# Shining_Pig.net
KiCad netlist of a schematic drawn in Altium Designer
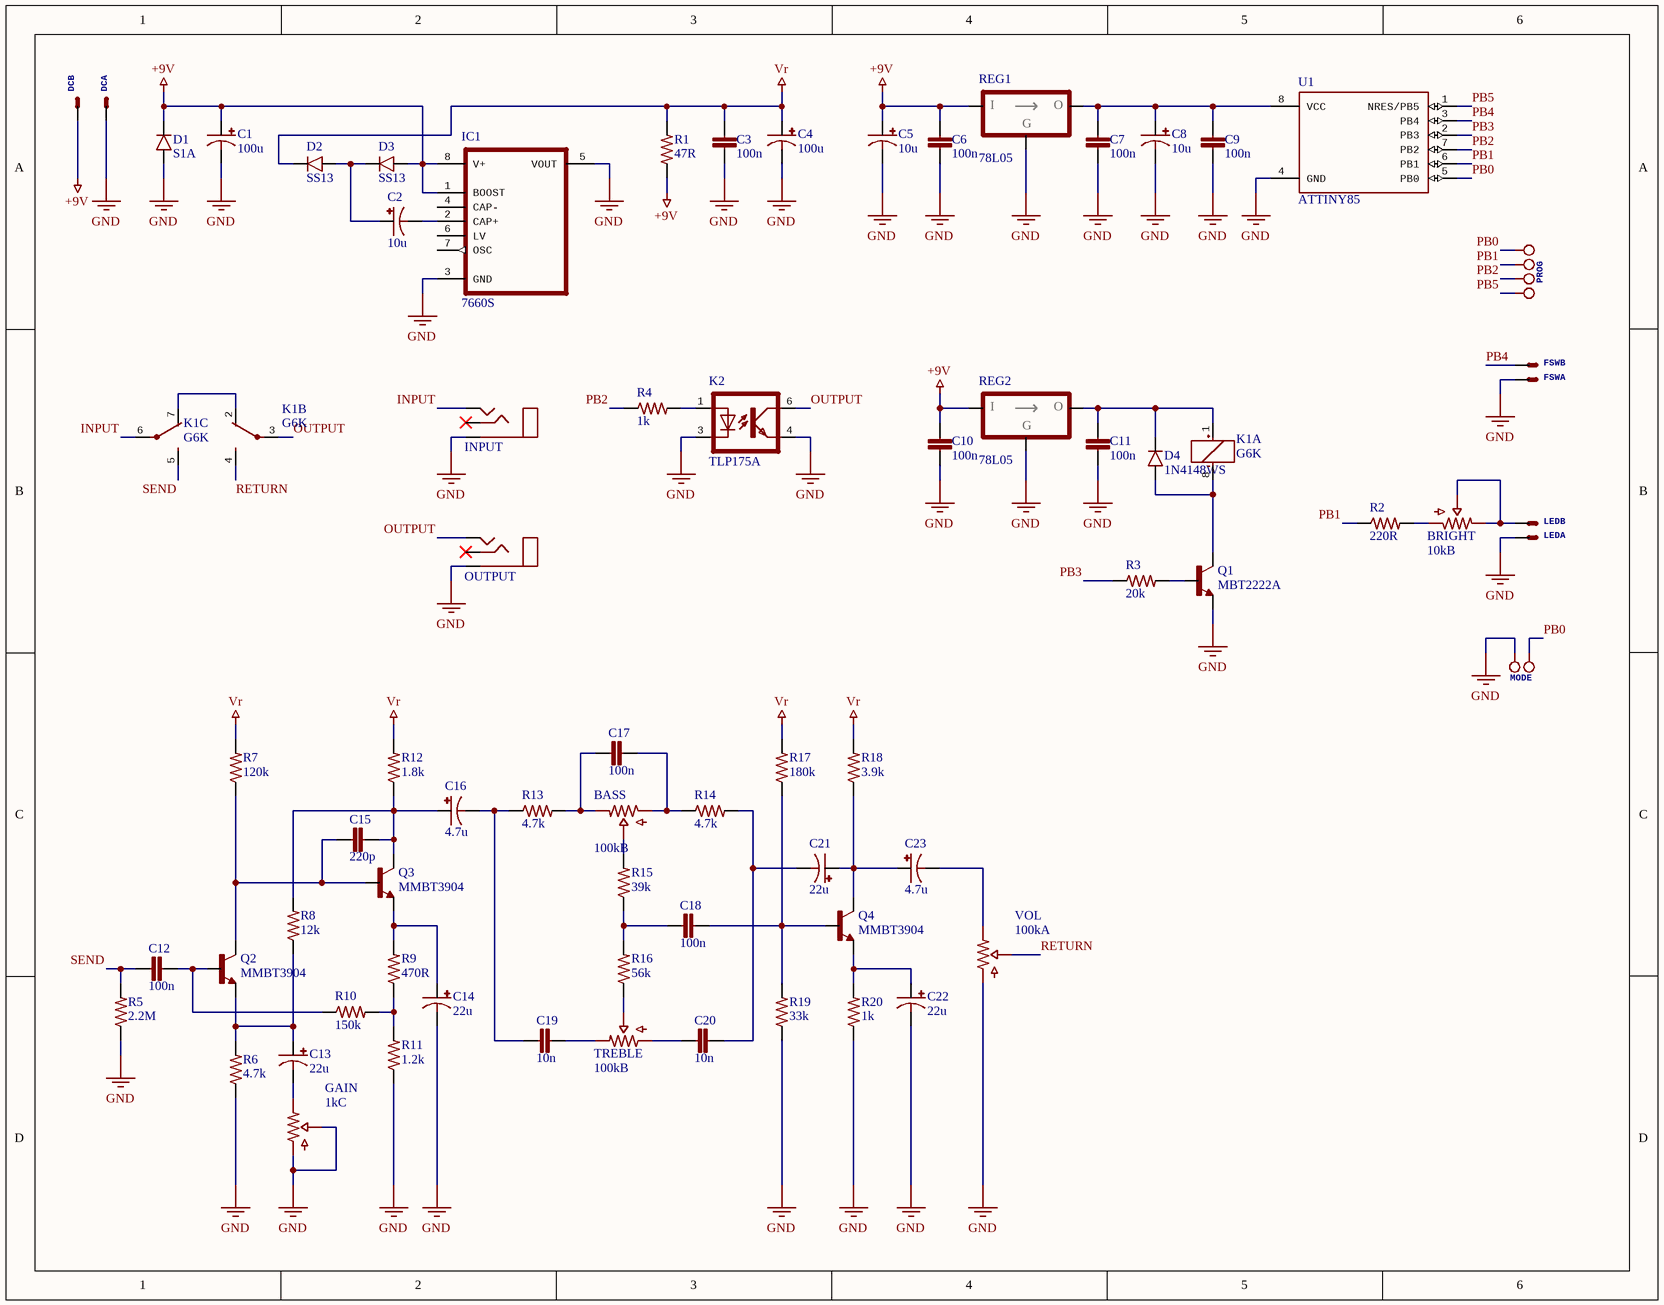
[diagram p0: Shining Pig.SchDoc]

(export (version "E")
  (design (tool "Eeschema 10.0.6"))
  (components
    (comp (ref "BASS")
      (value "100kB")
      (footprint "ALPHA_16mm_BOTTOM")
      (description "100k Lin potentiometer round shaft")
      (libsource (lib "Pedals") (part "POT_100kB_ALPHA_16mm"))
    )
    (comp (ref "BRIGHT")
      (value "10kB")
      (footprint "BOURNS_3362P")
      (description "10k Lin 3362P trimmer")
      (libsource (lib "Pedals") (part "TRIM_10kB_3362P"))
    )
    (comp (ref "C1")
      (value "100u")
      (footprint "CAPAE_D")
      (description "CAP ALUM 100UF 25V SMD")
      (fields
        (field (name "MANUFACTURER") "Multicomp")
        (field (name "MANUFACTURER PART NUMBER") "MCVVT025M101EA6L")
      )
      (libsource (lib "Pedals SMD") (part "MCVVT025M101EA6L"))
    )
    (comp (ref "C2")
      (value "10u")
      (footprint "CAPAE_B")
      (description "CAP ALUM 10UF 25V SMD")
      (fields
        (field (name "MANUFACTURER") "Multicomp")
        (field (name "MANUFACTURER PART NUMBER") "MCVVT025M100CA1L")
      )
      (libsource (lib "") (part "MCVVT025M100CA1L_1"))
    )
    (comp (ref "C3")
      (value "100n")
      (footprint "CHIP_0603")
      (description "CAP CER 100NF 50V X7R 0603")
      (fields
        (field (name "MANUFACTURER") "Multicomp")
        (field (name "MANUFACTURER PART NUMBER") "MC0603B104K500CT")
      )
      (libsource (lib "Pedals SMD") (part "MC0603B104K500CT"))
    )
    (comp (ref "C4")
      (value "100u")
      (footprint "CAPAE_D")
      (description "CAP ALUM 100UF 25V SMD")
      (fields
        (field (name "MANUFACTURER") "Multicomp")
        (field (name "MANUFACTURER PART NUMBER") "MCVVT025M101EA6L")
      )
      (libsource (lib "Pedals SMD") (part "MCVVT025M101EA6L"))
    )
    (comp (ref "C5")
      (value "10u")
      (footprint "CAPAE_B")
      (description "CAP ALUM 10UF 25V SMD")
      (fields
        (field (name "MANUFACTURER") "Multicomp")
        (field (name "MANUFACTURER PART NUMBER") "MCVVT025M100CA1L")
      )
      (libsource (lib "Pedals SMD") (part "MCVVT025M100CA1L"))
    )
    (comp (ref "C6")
      (value "100n")
      (footprint "CHIP_0603")
      (description "CAP CER 100NF 50V X7R 0603")
      (fields
        (field (name "MANUFACTURER") "Multicomp")
        (field (name "MANUFACTURER PART NUMBER") "MC0603B104K500CT")
      )
      (libsource (lib "Pedals SMD") (part "MC0603B104K500CT"))
    )
    (comp (ref "C7")
      (value "100n")
      (footprint "CHIP_0603")
      (description "CAP CER 100NF 50V X7R 0603")
      (fields
        (field (name "MANUFACTURER") "Multicomp")
        (field (name "MANUFACTURER PART NUMBER") "MC0603B104K500CT")
      )
      (libsource (lib "Pedals SMD") (part "MC0603B104K500CT"))
    )
    (comp (ref "C8")
      (value "10u")
      (footprint "CAPAE_B")
      (description "CAP ALUM 10UF 25V SMD")
      (fields
        (field (name "MANUFACTURER") "Multicomp")
        (field (name "MANUFACTURER PART NUMBER") "MCVVT025M100CA1L")
      )
      (libsource (lib "Pedals SMD") (part "MCVVT025M100CA1L"))
    )
    (comp (ref "C9")
      (value "100n")
      (footprint "CHIP_0603")
      (description "CAP CER 100NF 50V X7R 0603")
      (fields
        (field (name "MANUFACTURER") "Multicomp")
        (field (name "MANUFACTURER PART NUMBER") "MC0603B104K500CT")
      )
      (libsource (lib "Pedals SMD") (part "MC0603B104K500CT"))
    )
    (comp (ref "C10")
      (value "100n")
      (footprint "CHIP_0603")
      (description "CAP CER 100NF 50V X7R 0603")
      (fields
        (field (name "MANUFACTURER") "Multicomp")
        (field (name "MANUFACTURER PART NUMBER") "MC0603B104K500CT")
      )
      (libsource (lib "Pedals SMD") (part "MC0603B104K500CT"))
    )
    (comp (ref "C11")
      (value "100n")
      (footprint "CHIP_0603")
      (description "CAP CER 100NF 50V X7R 0603")
      (fields
        (field (name "MANUFACTURER") "Multicomp")
        (field (name "MANUFACTURER PART NUMBER") "MC0603B104K500CT")
      )
      (libsource (lib "Pedals SMD") (part "MC0603B104K500CT"))
    )
    (comp (ref "C12")
      (value "100n")
      (footprint "CHIP_1206")
      (description "CAP CER 100NF 50V C0G/NP0 1206")
      (fields
        (field (name "MANUFACTURER") "Murata")
        (field (name "MANUFACTURER PART NUMBER") "GRM31C5C1H104JA01L")
      )
      (libsource (lib "Pedals SMD") (part "GRM31C5C1H104JA01L"))
    )
    (comp (ref "C13")
      (value "22u")
      (footprint "CAPAE_D")
      (description "CAP ALUM 22UF 20% 35V LESR SMD")
      (fields
        (field (name "MANUFACTURER") "Panasonic")
        (field (name "MANUFACTURER PART NUMBER") "EEEFC1V220AP")
      )
      (libsource (lib "") (part "EEEFC1V220AP_1"))
    )
    (comp (ref "C14")
      (value "22u")
      (footprint "CAPAE_D")
      (description "CAP ALUM 22UF 20% 35V LESR SMD")
      (fields
        (field (name "MANUFACTURER") "Panasonic")
        (field (name "MANUFACTURER PART NUMBER") "EEEFC1V220AP")
      )
      (libsource (lib "") (part "EEEFC1V220AP_1"))
    )
    (comp (ref "C15")
      (value "220p")
      (footprint "CHIP_0603")
      (description "CAP CER 220PF 50V C0G/NP0 0603")
      (fields
        (field (name "MANUFACTURER") "Multicomp")
        (field (name "MANUFACTURER PART NUMBER") "MC0603N221J500CT")
      )
      (libsource (lib "Pedals SMD") (part "MC0603N221J500CT"))
    )
    (comp (ref "C16")
      (value "4.7u")
      (footprint "CAPAE_C")
      (description "CAP ALUM 4.7UF 50V LESR SMD")
      (fields
        (field (name "MANUFACTURER") "Panasonic")
        (field (name "MANUFACTURER PART NUMBER") "EEEFC1H4R7R")
      )
      (libsource (lib "Pedals SMD") (part "EEEFC1H4R7R"))
    )
    (comp (ref "C17")
      (value "100n")
      (footprint "CHIP_1206")
      (description "CAP CER 100NF 50V C0G/NP0 1206")
      (fields
        (field (name "MANUFACTURER") "Murata")
        (field (name "MANUFACTURER PART NUMBER") "GRM31C5C1H104JA01L")
      )
      (libsource (lib "Pedals SMD") (part "GRM31C5C1H104JA01L"))
    )
    (comp (ref "C18")
      (value "100n")
      (footprint "CHIP_1206")
      (description "CAP CER 100NF 50V C0G/NP0 1206")
      (fields
        (field (name "MANUFACTURER") "Murata")
        (field (name "MANUFACTURER PART NUMBER") "GRM31C5C1H104JA01L")
      )
      (libsource (lib "Pedals SMD") (part "GRM31C5C1H104JA01L"))
    )
    (comp (ref "C19")
      (value "10n")
      (footprint "CHIP_0603")
      (description "CAP CER 10NF 50V C0G/NP0 0603")
      (fields
        (field (name "MANUFACTURER") "Murata")
        (field (name "MANUFACTURER PART NUMBER") "GRM1885C1H103JA01D")
      )
      (libsource (lib "Pedals SMD") (part "GRM1885C1H103JA01D"))
    )
    (comp (ref "C20")
      (value "10n")
      (footprint "CHIP_0603")
      (description "CAP CER 10NF 50V C0G/NP0 0603")
      (fields
        (field (name "MANUFACTURER") "Murata")
        (field (name "MANUFACTURER PART NUMBER") "GRM1885C1H103JA01D")
      )
      (libsource (lib "Pedals SMD") (part "GRM1885C1H103JA01D"))
    )
    (comp (ref "C21")
      (value "22u")
      (footprint "CAPAE_D")
      (description "CAP ALUM 22UF 20% 35V LESR SMD")
      (fields
        (field (name "MANUFACTURER") "Panasonic")
        (field (name "MANUFACTURER PART NUMBER") "EEEFC1V220AP")
      )
      (libsource (lib "Pedals SMD") (part "EEEFC1V220AP"))
    )
    (comp (ref "C22")
      (value "22u")
      (footprint "CAPAE_D")
      (description "CAP ALUM 22UF 20% 35V LESR SMD")
      (fields
        (field (name "MANUFACTURER") "Panasonic")
        (field (name "MANUFACTURER PART NUMBER") "EEEFC1V220AP")
      )
      (libsource (lib "") (part "EEEFC1V220AP_1"))
    )
    (comp (ref "C23")
      (value "4.7u")
      (footprint "CAPAE_C")
      (description "CAP ALUM 4.7UF 50V LESR SMD")
      (fields
        (field (name "MANUFACTURER") "Panasonic")
        (field (name "MANUFACTURER PART NUMBER") "EEEFC1H4R7R")
      )
      (libsource (lib "Pedals SMD") (part "EEEFC1H4R7R"))
    )
    (comp (ref "D1")
      (value "S1A")
      (footprint "DO214")
      (description "DIODE GEN PURP 50V 1A SMA")
      (fields (field (name "MANUFACTURER") "ON Semiconductor / Fairchild"))
      (libsource (lib "Pedals SMD") (part "S1A"))
    )
    (comp (ref "D2")
      (value "SS13")
      (footprint "SOD123F")
      (description "DIODE SCHOTTKY 30V 1A SOD123F")
      (fields
        (field (name "MANUFACTURER") "ON Semiconductor / Fairchild")
        (field (name "MANUFACTURER PART NUMBER") "SS13FL")
      )
      (libsource (lib "Pedals SMD") (part "SS13FL"))
    )
    (comp (ref "D3")
      (value "SS13")
      (footprint "SOD123F")
      (description "DIODE SCHOTTKY 30V 1A SOD123F")
      (fields
        (field (name "MANUFACTURER") "ON Semiconductor / Fairchild")
        (field (name "MANUFACTURER PART NUMBER") "SS13FL")
      )
      (libsource (lib "Pedals SMD") (part "SS13FL"))
    )
    (comp (ref "D4")
      (value "1N4148WS")
      (footprint "SOD323")
      (description "DIODE GEN PURP 75V 150MA SOD323F")
      (fields (field (name "MANUFACTURER") "ON Semiconductor / Fairchild"))
      (libsource (lib "Pedals SMD") (part "1N4148WS"))
    )
    (comp (ref "DC")
      (value "J_JST-XH-02")
      (footprint "JST-XH-02")
      (description "2 Pins male XH header")
      (libsource (lib "Pedals") (part "J_JST-XH-02"))
    )
    (comp (ref "FSW")
      (value "J_JST-XH-02")
      (footprint "JST-XH-02")
      (description "2 Pins male XH header")
      (libsource (lib "Pedals") (part "J_JST-XH-02"))
    )
    (comp (ref "GAIN")
      (value "1kC")
      (footprint "ALPHA_16mm_BOTTOM")
      (description "1k Reverse log potentiometer round shaft")
      (libsource (lib "Pedals") (part "POT_1kC_ALPHA_16mm"))
    )
    (comp (ref "IC1")
      (value "7660S")
      (footprint "SO8")
      (description "RENESAS - ICL7660SCBAZ - IC DC DC CHARGE PUMP")
      (fields
        (field (name "MANUFACTURER") "Intersil")
        (field (name "MANUFACTURER PART NUMBER") "ICL7660SCBAZ")
      )
      (libsource (lib "Pedals SMD") (part "ICL7660SCBAZ"))
    )
    (comp (ref "INPUT")
      (value "J_STEREO")
      (footprint "STEREO")
      (description "6.35mm stereo insulated socket jack PCB mounted")
      (libsource (lib "Pedals") (part "J_STEREO"))
    )
    (comp (ref "K1")
      (value "G6K")
      (footprint "G6K")
      (description "OMRON - G6K-2F 5DC - RELAY, SIGNAL, DPDT, 30VDC, 1A")
      (fields (field (name "MANUFACTURER") "Cliff") (field (name "MANUFACTURER PART NUMBER") "G6K-2F5DC"))
      (libsource (lib "") (part "G6K-2F5DC_2"))
    )
    (comp (ref "K2")
      (value "TLP175A")
      (footprint "TLP175A")
      (description "Toshiba TLP175A AC Input MOSFET Output Optocoupler, Surface Mount, 4-Pin SOIC")
      (fields (field (name "MANUFACTURER") "Toshiba"))
      (libsource (lib "Pedals SMD") (part "TLP175A"))
    )
    (comp (ref "LED")
      (value "J_JST-XH-02")
      (footprint "JST-XH-02")
      (description "2 Pins male XH header")
      (libsource (lib "Pedals") (part "J_JST-XH-02"))
    )
    (comp (ref "MODE")
      (value "J_HEADER_2PINS")
      (footprint "HEADER_2PINS")
      (description "2 Pins male header")
      (libsource (lib "Pedals") (part "J_HEADER_2PINS"))
    )
    (comp (ref "OUTPUT")
      (value "J_STEREO")
      (footprint "STEREO")
      (description "6.35mm stereo insulated socket jack PCB mounted")
      (libsource (lib "Pedals") (part "J_STEREO"))
    )
    (comp (ref "PROG")
      (value "J_HEADER_4PINS_FEM")
      (footprint "HEADER_4Pins_FEM")
      (description "4 Pins female header")
      (libsource (lib "Pedals") (part "J_HEADER_4PINS_FEM"))
    )
    (comp (ref "Q1")
      (value "MBT2222A")
      (footprint "SOT323")
      (description "TRANS NPN 40V 0.6A SOT323")
      (fields
        (field (name "MANUFACTURER") "ON Semiconductor")
        (field (name "MANUFACTURER PART NUMBER") "MMBT2222AWT1G")
      )
      (libsource (lib "Pedals SMD") (part "MMBT2222AWT1G"))
    )
    (comp (ref "Q2")
      (value "MMBT3904")
      (footprint "SOT23")
      (description "TRANS NPN 40V 0.2A SOT23")
      (fields
        (field (name "MANUFACTURER") "ON Semiconductor")
        (field (name "MANUFACTURER PART NUMBER") "MMBT3904LT1G")
      )
      (libsource (lib "Pedals SMD") (part "MMBT3904LT1G"))
    )
    (comp (ref "Q3")
      (value "MMBT3904")
      (footprint "SOT23")
      (description "TRANS NPN 40V 0.2A SOT23")
      (fields
        (field (name "MANUFACTURER") "ON Semiconductor")
        (field (name "MANUFACTURER PART NUMBER") "MMBT3904LT1G")
      )
      (libsource (lib "Pedals SMD") (part "MMBT3904LT1G"))
    )
    (comp (ref "Q4")
      (value "MMBT3904")
      (footprint "SOT23")
      (description "TRANS NPN 40V 0.2A SOT23")
      (fields
        (field (name "MANUFACTURER") "ON Semiconductor")
        (field (name "MANUFACTURER PART NUMBER") "MMBT3904LT1G")
      )
      (libsource (lib "Pedals SMD") (part "MMBT3904LT1G"))
    )
    (comp (ref "R1")
      (value "47R")
      (footprint "CHIP_R_1206")
      (description "RES SMD 47 OHM 1% 1/4W 1206")
      (fields
        (field (name "MANUFACTURER") "Vishay")
        (field (name "MANUFACTURER PART NUMBER") "CRCW120647R0FKEA")
      )
      (libsource (lib "Pedals SMD") (part "CRCW120647R0FKEA"))
    )
    (comp (ref "R2")
      (value "220R")
      (footprint "CHIP_R_1206")
      (description "RES SMD 220 OHM 1% 1/4W 1206")
      (fields
        (field (name "MANUFACTURER") "Vishay")
        (field (name "MANUFACTURER PART NUMBER") "CRCW1206220RFKEA")
      )
      (libsource (lib "Pedals SMD") (part "CRCW1206220RFKEA"))
    )
    (comp (ref "R3")
      (value "20k")
      (footprint "CHIP_R_0603")
      (description "RES SMD 20K OHM 1% 1/10W 0603")
      (fields
        (field (name "MANUFACTURER") "Vishay")
        (field (name "MANUFACTURER PART NUMBER") "CRCW060320K0FKEA")
      )
      (libsource (lib "Pedals SMD") (part "CRCW060320K0FKEA"))
    )
    (comp (ref "R4")
      (value "1k")
      (footprint "CHIP_R_0603")
      (description "RES SMD 1K OHM 1% 1/10W 0603")
      (fields
        (field (name "MANUFACTURER") "Vishay Dale")
        (field (name "MANUFACTURER PART NUMBER") "CRCW06031K00FKEA")
      )
      (libsource (lib "Pedals SMD") (part "CRCW06031K00FKEA"))
    )
    (comp (ref "R5")
      (value "2.2M")
      (footprint "CHIP_R_0603")
      (description "RES SMD 2.2M OHM 1% 1/10W 0603")
      (fields
        (field (name "MANUFACTURER") "Vishay")
        (field (name "MANUFACTURER PART NUMBER") "CRCW06032M20FKEA")
      )
      (libsource (lib "Pedals SMD") (part "CRCW06032M20FKEA"))
    )
    (comp (ref "R6")
      (value "4.7k")
      (footprint "CHIP_R_0603")
      (description "RES SMD 4.7K OHM 1% 1/10W 0603")
      (fields
        (field (name "MANUFACTURER") "Vishay")
        (field (name "MANUFACTURER PART NUMBER") "CRCW06034K70FKEA")
      )
      (libsource (lib "Pedals SMD") (part "CRCW06034K70FKEA"))
    )
    (comp (ref "R7")
      (value "120k")
      (footprint "CHIP_R_1206")
      (description "RES SMD 120K OHM 1% 1/4W 1206")
      (fields
        (field (name "MANUFACTURER") "Vishay")
        (field (name "MANUFACTURER PART NUMBER") "CRCW1206120KFKEA")
      )
      (libsource (lib "Pedals SMD") (part "CRCW1206120KFKEA"))
    )
    (comp (ref "R8")
      (value "12k")
      (footprint "CHIP_R_0603")
      (description "RES SMD 12K OHM 1% 1/10W 0603")
      (fields
        (field (name "MANUFACTURER") "Vishay")
        (field (name "MANUFACTURER PART NUMBER") "CRCW060312K0FKEA")
      )
      (libsource (lib "Pedals SMD") (part "CRCW060312K0FKEA"))
    )
    (comp (ref "R9")
      (value "470R")
      (footprint "CHIP_R_0603")
      (description "RES SMD 470 OHM 1% 1/10W 0603")
      (fields
        (field (name "MANUFACTURER") "Vishay")
        (field (name "MANUFACTURER PART NUMBER") "CRCW0603470RFKEA")
      )
      (libsource (lib "Pedals SMD") (part "CRCW0603470RFKEA"))
    )
    (comp (ref "R10")
      (value "150k")
      (footprint "CHIP_R_0603")
      (description "RES SMD 150K OHM 1% 1/10W 0603")
      (fields
        (field (name "MANUFACTURER") "Vishay")
        (field (name "MANUFACTURER PART NUMBER") "CRCW0603150KFKEA")
      )
      (libsource (lib "Pedals SMD") (part "CRCW0603150KFKEA"))
    )
    (comp (ref "R11")
      (value "1.2k")
      (footprint "CHIP_R_0603")
      (description "RES SMD 1.2K OHM 1% 1/10W 0603")
      (fields
        (field (name "MANUFACTURER") "Vishay")
        (field (name "MANUFACTURER PART NUMBER") "CRCW06031K20FKEA")
      )
      (libsource (lib "Pedals SMD") (part "CRCW06031K20FKEA"))
    )
    (comp (ref "R12")
      (value "1.8k")
      (footprint "CHIP_R_1206")
      (description "RES SMD 1.8K OHM 1% 1/4W 1206")
      (fields
        (field (name "MANUFACTURER") "Vishay")
        (field (name "MANUFACTURER PART NUMBER") "CRCW12061K80FKEA")
      )
      (libsource (lib "Pedals SMD") (part "CRCW12061K80FKEA"))
    )
    (comp (ref "R13")
      (value "4.7k")
      (footprint "CHIP_R_0603")
      (description "RES SMD 4.7K OHM 1% 1/10W 0603")
      (fields
        (field (name "MANUFACTURER") "Vishay")
        (field (name "MANUFACTURER PART NUMBER") "CRCW06034K70FKEA")
      )
      (libsource (lib "Pedals SMD") (part "CRCW06034K70FKEA"))
    )
    (comp (ref "R14")
      (value "4.7k")
      (footprint "CHIP_R_0603")
      (description "RES SMD 4.7K OHM 1% 1/10W 0603")
      (fields
        (field (name "MANUFACTURER") "Vishay")
        (field (name "MANUFACTURER PART NUMBER") "CRCW06034K70FKEA")
      )
      (libsource (lib "Pedals SMD") (part "CRCW06034K70FKEA"))
    )
    (comp (ref "R15")
      (value "39k")
      (footprint "CHIP_R_0603")
      (description "RES SMD 39K OHM 1% 1/10W 0603")
      (fields
        (field (name "MANUFACTURER") "Vishay")
        (field (name "MANUFACTURER PART NUMBER") "CRCW060339K0FKEA")
      )
      (libsource (lib "Pedals SMD") (part "CRCW060339K0FKEA"))
    )
    (comp (ref "R16")
      (value "56k")
      (footprint "CHIP_R_0603")
      (description "RES SMD 5.6K OHM 1% 1/10W 0603")
      (fields
        (field (name "MANUFACTURER") "Vishay")
        (field (name "MANUFACTURER PART NUMBER") "CRCW06035K60FKEA")
      )
      (libsource (lib "Pedals SMD") (part "CRCW06035K60FKEA"))
    )
    (comp (ref "R17")
      (value "180k")
      (footprint "CHIP_R_1206")
      (description "RES SMD 180K OHM 1% 1/4W 1206")
      (fields
        (field (name "MANUFACTURER") "Vishay")
        (field (name "MANUFACTURER PART NUMBER") "CRCW1206180KFKEA")
      )
      (libsource (lib "Pedals SMD") (part "CRCW1206180KFKEA"))
    )
    (comp (ref "R18")
      (value "3.9k")
      (footprint "CHIP_R_1206")
      (description "RES SMD 3.9K OHM 1% 1/4W 1206")
      (fields
        (field (name "MANUFACTURER") "Vishay")
        (field (name "MANUFACTURER PART NUMBER") "CRCW12063K90FKEA")
      )
      (libsource (lib "Pedals SMD") (part "CRCW12063K90FKEA"))
    )
    (comp (ref "R19")
      (value "33k")
      (footprint "CHIP_R_0603")
      (description "RES SMD 33K OHM 1% 1/10W 0603")
      (fields
        (field (name "MANUFACTURER") "Vishay")
        (field (name "MANUFACTURER PART NUMBER") "CRCW060333K0FKEA")
      )
      (libsource (lib "Pedals SMD") (part "CRCW060333K0FKEA"))
    )
    (comp (ref "R20")
      (value "1k")
      (footprint "CHIP_R_0603")
      (description "RES SMD 1K OHM 1% 1/10W 0603")
      (fields
        (field (name "MANUFACTURER") "Vishay Dale")
        (field (name "MANUFACTURER PART NUMBER") "CRCW06031K00FKEA")
      )
      (libsource (lib "Pedals SMD") (part "CRCW06031K00FKEA"))
    )
    (comp (ref "REG1")
      (value "78L05")
      (footprint "SOT23-3")
      (description "TAIWAN SEMICONDUCTOR - TS78L05CX RFG - REG 3-TERMINAL 100MA, SMD, SOT23-3")
      (fields
        (field (name "MANUFACTURER") "Taiwan Semiconductor")
        (field (name "MANUFACTURER PART NUMBER") "TS78L05CXRFG")
      )
      (libsource (lib "Pedals SMD") (part "TS78L05CXRFG"))
    )
    (comp (ref "REG2")
      (value "78L05")
      (footprint "SOT23-3")
      (description "TAIWAN SEMICONDUCTOR - TS78L05CX RFG - REG 3-TERMINAL 100MA, SMD, SOT23-3")
      (fields
        (field (name "MANUFACTURER") "Taiwan Semiconductor")
        (field (name "MANUFACTURER PART NUMBER") "TS78L05CXRFG")
      )
      (libsource (lib "Pedals SMD") (part "TS78L05CXRFG"))
    )
    (comp (ref "TREBLE")
      (value "100kB")
      (footprint "ALPHA_16mm_BOTTOM")
      (description "100k Lin potentiometer round shaft")
      (libsource (lib "Pedals") (part "POT_100kB_ALPHA_16mm"))
    )
    (comp (ref "U1")
      (value "ATTINY85")
      (footprint "SOP8")
      (description "IC, 8BIT MCU, AVR TINY, 20MHZ, 8-SOIC")
      (fields
        (field (name "MANUFACTURER") "Microchip / Atmel")
        (field (name "MANUFACTURER PART NUMBER") "ATTINY85-20SU")
      )
      (libsource (lib "Pedals SMD") (part "ATTINY85-20SU"))
    )
    (comp (ref "VOL")
      (value "100kA")
      (footprint "ALPHA_16mm_BOTTOM")
      (description "100k Log potentiometer round shaft")
      (libsource (lib "Pedals") (part "POT_100kA_ALPHA_16mm"))
    )
  )
  (nets
    (net (code "1") (name "+9V") (class "Default")
      (node (ref "C1") (pin "+") (pinfunction "+_+") (pintype "passive"))
      (node (ref "C10") (pin "1") (pinfunction "1_1") (pintype "passive"))
      (node (ref "C5") (pin "+") (pinfunction "+_+") (pintype "passive"))
      (node (ref "C6") (pin "1") (pinfunction "1_1") (pintype "passive"))
      (node (ref "D1") (pin "1") (pinfunction "1_1") (pintype "passive"))
      (node (ref "D3") (pin "2") (pinfunction "2_2") (pintype "passive"))
      (node (ref "DC") (pin "1") (pinfunction "S_1") (pintype "passive"))
      (node (ref "IC1") (pin "1") (pinfunction "BOOST_1") (pintype "power_in"))
      (node (ref "IC1") (pin "8") (pinfunction "V+_8") (pintype "power_in"))
      (node (ref "R1") (pin "1") (pinfunction "1_1") (pintype "passive"))
      (node (ref "REG1") (pin "2") (pinfunction "INPUT_2") (pintype "power_in"))
      (node (ref "REG2") (pin "2") (pinfunction "INPUT_2") (pintype "power_in"))
    )
    (net (code "2") (name "/INPUT") (class "Default")
      (node (ref "INPUT") (pin "T") (pinfunction "T_T") (pintype "passive"))
      (node (ref "K1") (pin "6") (pinfunction "P_6") (pintype "passive"))
    )
    (net (code "3") (name "/OUTPUT") (class "Default")
      (node (ref "K1") (pin "3") (pinfunction "P_3") (pintype "passive"))
      (node (ref "K2") (pin "6") (pinfunction "COL_6") (pintype "passive"))
      (node (ref "OUTPUT") (pin "T") (pinfunction "T_T") (pintype "passive"))
    )
    (net (code "4") (name "/PB0") (class "Default")
      (node (ref "MODE") (pin "2") (pinfunction "2_2") (pintype "passive"))
      (node (ref "PROG") (pin "4") (pinfunction "4_4") (pintype "passive"))
      (node (ref "U1") (pin "5") (pinfunction "PB0_5") (pintype "bidirectional"))
    )
    (net (code "5") (name "/PB1") (class "Default")
      (node (ref "PROG") (pin "3") (pinfunction "3_3") (pintype "passive"))
      (node (ref "R2") (pin "1") (pinfunction "1_1") (pintype "passive"))
      (node (ref "U1") (pin "6") (pinfunction "PB1_6") (pintype "bidirectional"))
    )
    (net (code "6") (name "/PB2") (class "Default")
      (node (ref "PROG") (pin "2") (pinfunction "2_2") (pintype "passive"))
      (node (ref "R4") (pin "1") (pinfunction "1_1") (pintype "passive"))
      (node (ref "U1") (pin "7") (pinfunction "PB2_7") (pintype "bidirectional"))
    )
    (net (code "7") (name "/PB3") (class "Default")
      (node (ref "R3") (pin "1") (pinfunction "1_1") (pintype "passive"))
      (node (ref "U1") (pin "2") (pinfunction "PB3_2") (pintype "bidirectional"))
    )
    (net (code "8") (name "/PB4") (class "Default")
      (node (ref "FSW") (pin "1") (pinfunction "S_1") (pintype "passive"))
      (node (ref "U1") (pin "3") (pinfunction "PB4_3") (pintype "bidirectional"))
    )
    (net (code "9") (name "/PB5") (class "Default")
      (node (ref "PROG") (pin "1") (pinfunction "1_1") (pintype "passive"))
      (node (ref "U1") (pin "1") (pinfunction "NRES/PB5_1") (pintype "bidirectional"))
    )
    (net (code "10") (name "/RETURN") (class "Default")
      (node (ref "K1") (pin "4") (pinfunction "S_4") (pintype "passive"))
      (node (ref "VOL") (pin "2") (pinfunction "2_2") (pintype "passive"))
    )
    (net (code "11") (name "/SEND") (class "Default")
      (node (ref "C12") (pin "2") (pinfunction "2_2") (pintype "passive"))
      (node (ref "K1") (pin "5") (pinfunction "S_5") (pintype "passive"))
      (node (ref "R5") (pin "2") (pinfunction "2_2") (pintype "passive"))
    )
    (net (code "12") (name "GND") (class "Default")
      (node (ref "C1") (pin "-") (pinfunction "-_-") (pintype "passive"))
      (node (ref "C10") (pin "2") (pinfunction "2_2") (pintype "passive"))
      (node (ref "C11") (pin "2") (pinfunction "2_2") (pintype "passive"))
      (node (ref "C14") (pin "-") (pinfunction "-_-") (pintype "passive"))
      (node (ref "C22") (pin "-") (pinfunction "-_-") (pintype "passive"))
      (node (ref "C3") (pin "2") (pinfunction "2_2") (pintype "passive"))
      (node (ref "C4") (pin "-") (pinfunction "-_-") (pintype "passive"))
      (node (ref "C5") (pin "-") (pinfunction "-_-") (pintype "passive"))
      (node (ref "C6") (pin "2") (pinfunction "2_2") (pintype "passive"))
      (node (ref "C7") (pin "2") (pinfunction "2_2") (pintype "passive"))
      (node (ref "C8") (pin "-") (pinfunction "-_-") (pintype "passive"))
      (node (ref "C9") (pin "2") (pinfunction "2_2") (pintype "passive"))
      (node (ref "D1") (pin "2") (pinfunction "2_2") (pintype "passive"))
      (node (ref "DC") (pin "2") (pinfunction "S_2") (pintype "passive"))
      (node (ref "FSW") (pin "2") (pinfunction "S_2") (pintype "passive"))
      (node (ref "GAIN") (pin "1") (pinfunction "1_1") (pintype "passive"))
      (node (ref "GAIN") (pin "2") (pinfunction "2_2") (pintype "passive"))
      (node (ref "IC1") (pin "3") (pinfunction "GND_3") (pintype "power_in"))
      (node (ref "IC1") (pin "5") (pinfunction "VOUT_5") (pintype "power_in"))
      (node (ref "INPUT") (pin "S") (pinfunction "S_S") (pintype "passive"))
      (node (ref "K2") (pin "3") (pinfunction "C_3") (pintype "passive"))
      (node (ref "K2") (pin "4") (pinfunction "EMIT_4") (pintype "passive"))
      (node (ref "LED") (pin "2") (pinfunction "S_2") (pintype "passive"))
      (node (ref "MODE") (pin "1") (pinfunction "1_1") (pintype "passive"))
      (node (ref "OUTPUT") (pin "S") (pinfunction "S_S") (pintype "passive"))
      (node (ref "Q1") (pin "2") (pinfunction "E_2") (pintype "passive"))
      (node (ref "R11") (pin "1") (pinfunction "1_1") (pintype "passive"))
      (node (ref "R19") (pin "1") (pinfunction "1_1") (pintype "passive"))
      (node (ref "R20") (pin "1") (pinfunction "1_1") (pintype "passive"))
      (node (ref "R5") (pin "1") (pinfunction "1_1") (pintype "passive"))
      (node (ref "R6") (pin "1") (pinfunction "1_1") (pintype "passive"))
      (node (ref "REG1") (pin "3") (pinfunction "COMMON_3") (pintype "power_in"))
      (node (ref "REG2") (pin "3") (pinfunction "COMMON_3") (pintype "power_in"))
      (node (ref "U1") (pin "4") (pinfunction "GND_4") (pintype "power_in"))
      (node (ref "VOL") (pin "1") (pinfunction "1_1") (pintype "passive"))
    )
    (net (code "13") (name "Net-(BASS-Pad1)") (class "Default")
      (node (ref "BASS") (pin "1") (pinfunction "1_1") (pintype "passive"))
      (node (ref "C17") (pin "1") (pinfunction "1_1") (pintype "passive"))
      (node (ref "R14") (pin "1") (pinfunction "1_1") (pintype "passive"))
    )
    (net (code "14") (name "Net-(BASS-Pad2)") (class "Default")
      (node (ref "BASS") (pin "2") (pinfunction "2_2") (pintype "passive"))
      (node (ref "R15") (pin "2") (pinfunction "2_2") (pintype "passive"))
    )
    (net (code "15") (name "Net-(BASS-Pad3)") (class "Default")
      (node (ref "BASS") (pin "3") (pinfunction "3_3") (pintype "passive"))
      (node (ref "C17") (pin "2") (pinfunction "2_2") (pintype "passive"))
      (node (ref "R13") (pin "2") (pinfunction "2_2") (pintype "passive"))
    )
    (net (code "16") (name "Net-(BRIGHT-Pad1)") (class "Default")
      (node (ref "BRIGHT") (pin "1") (pinfunction "1_1") (pintype "passive"))
      (node (ref "R2") (pin "2") (pinfunction "2_2") (pintype "passive"))
    )
    (net (code "17") (name "Net-(C2-Pad+)") (class "Default")
      (node (ref "C2") (pin "+") (pinfunction "+_+") (pintype "passive"))
      (node (ref "D2") (pin "2") (pinfunction "2_2") (pintype "passive"))
      (node (ref "D3") (pin "1") (pinfunction "1_1") (pintype "passive"))
    )
    (net (code "18") (name "Net-(C13-Pad-)") (class "Default")
      (node (ref "C13") (pin "-") (pinfunction "-_-") (pintype "passive"))
      (node (ref "GAIN") (pin "3") (pinfunction "3_3") (pintype "passive"))
    )
    (net (code "19") (name "Net-(C16-Pad-)") (class "Default")
      (node (ref "C16") (pin "-") (pinfunction "-_-") (pintype "passive"))
      (node (ref "C19") (pin "2") (pinfunction "2_2") (pintype "passive"))
      (node (ref "R13") (pin "1") (pinfunction "1_1") (pintype "passive"))
    )
    (net (code "20") (name "Net-(C18-Pad2)") (class "Default")
      (node (ref "C18") (pin "2") (pinfunction "2_2") (pintype "passive"))
      (node (ref "R15") (pin "1") (pinfunction "1_1") (pintype "passive"))
      (node (ref "R16") (pin "2") (pinfunction "2_2") (pintype "passive"))
    )
    (net (code "21") (name "Net-(C19-Pad1)") (class "Default")
      (node (ref "C19") (pin "1") (pinfunction "1_1") (pintype "passive"))
      (node (ref "TREBLE") (pin "3") (pinfunction "3_3") (pintype "passive"))
    )
    (net (code "22") (name "Net-(C20-Pad1)") (class "Default")
      (node (ref "C20") (pin "1") (pinfunction "1_1") (pintype "passive"))
      (node (ref "C21") (pin "-") (pinfunction "-_-") (pintype "passive"))
      (node (ref "R14") (pin "2") (pinfunction "2_2") (pintype "passive"))
    )
    (net (code "23") (name "Net-(C20-Pad2)") (class "Default")
      (node (ref "C20") (pin "2") (pinfunction "2_2") (pintype "passive"))
      (node (ref "TREBLE") (pin "1") (pinfunction "1_1") (pintype "passive"))
    )
    (net (code "24") (name "Net-(C23-Pad-)") (class "Default")
      (node (ref "C23") (pin "-") (pinfunction "-_-") (pintype "passive"))
      (node (ref "VOL") (pin "3") (pinfunction "3_3") (pintype "passive"))
    )
    (net (code "25") (name "Net-(IC1-CAP+)") (class "Default")
      (node (ref "C2") (pin "-") (pinfunction "-_-") (pintype "passive"))
      (node (ref "IC1") (pin "2") (pinfunction "CAP+_2") (pintype "passive"))
    )
    (net (code "26") (name "Net-(K1A-+)") (class "Default")
      (node (ref "C11") (pin "1") (pinfunction "1_1") (pintype "passive"))
      (node (ref "D4") (pin "1") (pinfunction "1_1") (pintype "passive"))
      (node (ref "K1") (pin "1") (pinfunction "+_1") (pintype "passive"))
      (node (ref "REG2") (pin "1") (pinfunction "OUTPUT_1") (pintype "power_in"))
    )
    (net (code "27") (name "Net-(K1A--)") (class "Default")
      (node (ref "D4") (pin "2") (pinfunction "2_2") (pintype "passive"))
      (node (ref "K1") (pin "8") (pinfunction "-_8") (pintype "passive"))
      (node (ref "Q1") (pin "3") (pinfunction "C_3") (pintype "passive"))
    )
    (net (code "28") (name "Net-(K1B-O)") (class "Default")
      (node (ref "K1") (pin "2") (pinfunction "O_2") (pintype "passive"))
      (node (ref "K1") (pin "7") (pinfunction "O_7") (pintype "passive"))
    )
    (net (code "29") (name "Net-(K2-A)") (class "Default")
      (node (ref "K2") (pin "1") (pinfunction "A_1") (pintype "passive"))
      (node (ref "R4") (pin "2") (pinfunction "2_2") (pintype "passive"))
    )
    (net (code "30") (name "Net-(LEDB-S)") (class "Default")
      (node (ref "BRIGHT") (pin "2") (pinfunction "2_2") (pintype "passive"))
      (node (ref "BRIGHT") (pin "3") (pinfunction "3_3") (pintype "passive"))
      (node (ref "LED") (pin "1") (pinfunction "S_1") (pintype "passive"))
    )
    (net (code "31") (name "Net-(Q1-B)") (class "Default")
      (node (ref "Q1") (pin "1") (pinfunction "B_1") (pintype "passive"))
      (node (ref "R3") (pin "2") (pinfunction "2_2") (pintype "passive"))
    )
    (net (code "32") (name "Net-(Q2-B)") (class "Default")
      (node (ref "C12") (pin "1") (pinfunction "1_1") (pintype "passive"))
      (node (ref "Q2") (pin "1") (pinfunction "B_1") (pintype "passive"))
      (node (ref "R10") (pin "1") (pinfunction "1_1") (pintype "passive"))
    )
    (net (code "33") (name "Net-(Q2-C)") (class "Default")
      (node (ref "C15") (pin "2") (pinfunction "2_2") (pintype "passive"))
      (node (ref "Q2") (pin "3") (pinfunction "C_3") (pintype "passive"))
      (node (ref "Q3") (pin "1") (pinfunction "B_1") (pintype "passive"))
      (node (ref "R7") (pin "1") (pinfunction "1_1") (pintype "passive"))
    )
    (net (code "34") (name "Net-(Q2-E)") (class "Default")
      (node (ref "C13") (pin "+") (pinfunction "+_+") (pintype "passive"))
      (node (ref "Q2") (pin "2") (pinfunction "E_2") (pintype "passive"))
      (node (ref "R6") (pin "2") (pinfunction "2_2") (pintype "passive"))
      (node (ref "R8") (pin "1") (pinfunction "1_1") (pintype "passive"))
    )
    (net (code "35") (name "Net-(Q3-C)") (class "Default")
      (node (ref "C15") (pin "1") (pinfunction "1_1") (pintype "passive"))
      (node (ref "C16") (pin "+") (pinfunction "+_+") (pintype "passive"))
      (node (ref "Q3") (pin "3") (pinfunction "C_3") (pintype "passive"))
      (node (ref "R12") (pin "1") (pinfunction "1_1") (pintype "passive"))
      (node (ref "R8") (pin "2") (pinfunction "2_2") (pintype "passive"))
    )
    (net (code "36") (name "Net-(Q3-E)") (class "Default")
      (node (ref "C14") (pin "+") (pinfunction "+_+") (pintype "passive"))
      (node (ref "Q3") (pin "2") (pinfunction "E_2") (pintype "passive"))
      (node (ref "R9") (pin "2") (pinfunction "2_2") (pintype "passive"))
    )
    (net (code "37") (name "Net-(Q4-B)") (class "Default")
      (node (ref "C18") (pin "1") (pinfunction "1_1") (pintype "passive"))
      (node (ref "Q4") (pin "1") (pinfunction "B_1") (pintype "passive"))
      (node (ref "R17") (pin "1") (pinfunction "1_1") (pintype "passive"))
      (node (ref "R19") (pin "2") (pinfunction "2_2") (pintype "passive"))
    )
    (net (code "38") (name "Net-(Q4-C)") (class "Default")
      (node (ref "C21") (pin "+") (pinfunction "+_+") (pintype "passive"))
      (node (ref "C23") (pin "+") (pinfunction "+_+") (pintype "passive"))
      (node (ref "Q4") (pin "3") (pinfunction "C_3") (pintype "passive"))
      (node (ref "R18") (pin "1") (pinfunction "1_1") (pintype "passive"))
    )
    (net (code "39") (name "Net-(Q4-E)") (class "Default")
      (node (ref "C22") (pin "+") (pinfunction "+_+") (pintype "passive"))
      (node (ref "Q4") (pin "2") (pinfunction "E_2") (pintype "passive"))
      (node (ref "R20") (pin "2") (pinfunction "2_2") (pintype "passive"))
    )
    (net (code "40") (name "Net-(R10-Pad2)") (class "Default")
      (node (ref "R10") (pin "2") (pinfunction "2_2") (pintype "passive"))
      (node (ref "R11") (pin "2") (pinfunction "2_2") (pintype "passive"))
      (node (ref "R9") (pin "1") (pinfunction "1_1") (pintype "passive"))
    )
    (net (code "41") (name "Net-(R16-Pad1)") (class "Default")
      (node (ref "R16") (pin "1") (pinfunction "1_1") (pintype "passive"))
      (node (ref "TREBLE") (pin "2") (pinfunction "2_2") (pintype "passive"))
    )
    (net (code "42") (name "Net-(REG1-OUTPUT)") (class "Default")
      (node (ref "C7") (pin "1") (pinfunction "1_1") (pintype "passive"))
      (node (ref "C8") (pin "+") (pinfunction "+_+") (pintype "passive"))
      (node (ref "C9") (pin "1") (pinfunction "1_1") (pintype "passive"))
      (node (ref "REG1") (pin "1") (pinfunction "OUTPUT_1") (pintype "power_in"))
      (node (ref "U1") (pin "8") (pinfunction "VCC_8") (pintype "power_in"))
    )
    (net (code "43") (name "Vr") (class "Default")
      (node (ref "C3") (pin "1") (pinfunction "1_1") (pintype "passive"))
      (node (ref "C4") (pin "+") (pinfunction "+_+") (pintype "passive"))
      (node (ref "D2") (pin "1") (pinfunction "1_1") (pintype "passive"))
      (node (ref "R1") (pin "2") (pinfunction "2_2") (pintype "passive"))
      (node (ref "R12") (pin "2") (pinfunction "2_2") (pintype "passive"))
      (node (ref "R17") (pin "2") (pinfunction "2_2") (pintype "passive"))
      (node (ref "R18") (pin "2") (pinfunction "2_2") (pintype "passive"))
      (node (ref "R7") (pin "2") (pinfunction "2_2") (pintype "passive"))
    )
    (net (code "44") (name "unconnected-(IC1-CAP--Pad4)") (class "Default")
      (node (ref "IC1") (pin "4") (pinfunction "CAP-_4") (pintype "passive"))
    )
    (net (code "45") (name "unconnected-(IC1-LV-Pad6)") (class "Default")
      (node (ref "IC1") (pin "6") (pinfunction "LV_6") (pintype "passive"))
    )
    (net (code "46") (name "unconnected-(IC1-OSC-Pad7)") (class "Default")
      (node (ref "IC1") (pin "7") (pinfunction "OSC_7") (pintype "output"))
    )
    (net (code "47") (name "unconnected-(INPUT-PadR)") (class "Default")
      (node (ref "INPUT") (pin "R") (pinfunction "R_R") (pintype "passive+no_connect"))
    )
    (net (code "48") (name "unconnected-(OUTPUT-PadR)") (class "Default")
      (node (ref "OUTPUT") (pin "R") (pinfunction "R_R") (pintype "passive+no_connect"))
    )
  )
)
